# AgnusAdaptor.net
KiCad netlist of a schematic drawn in EAGLE
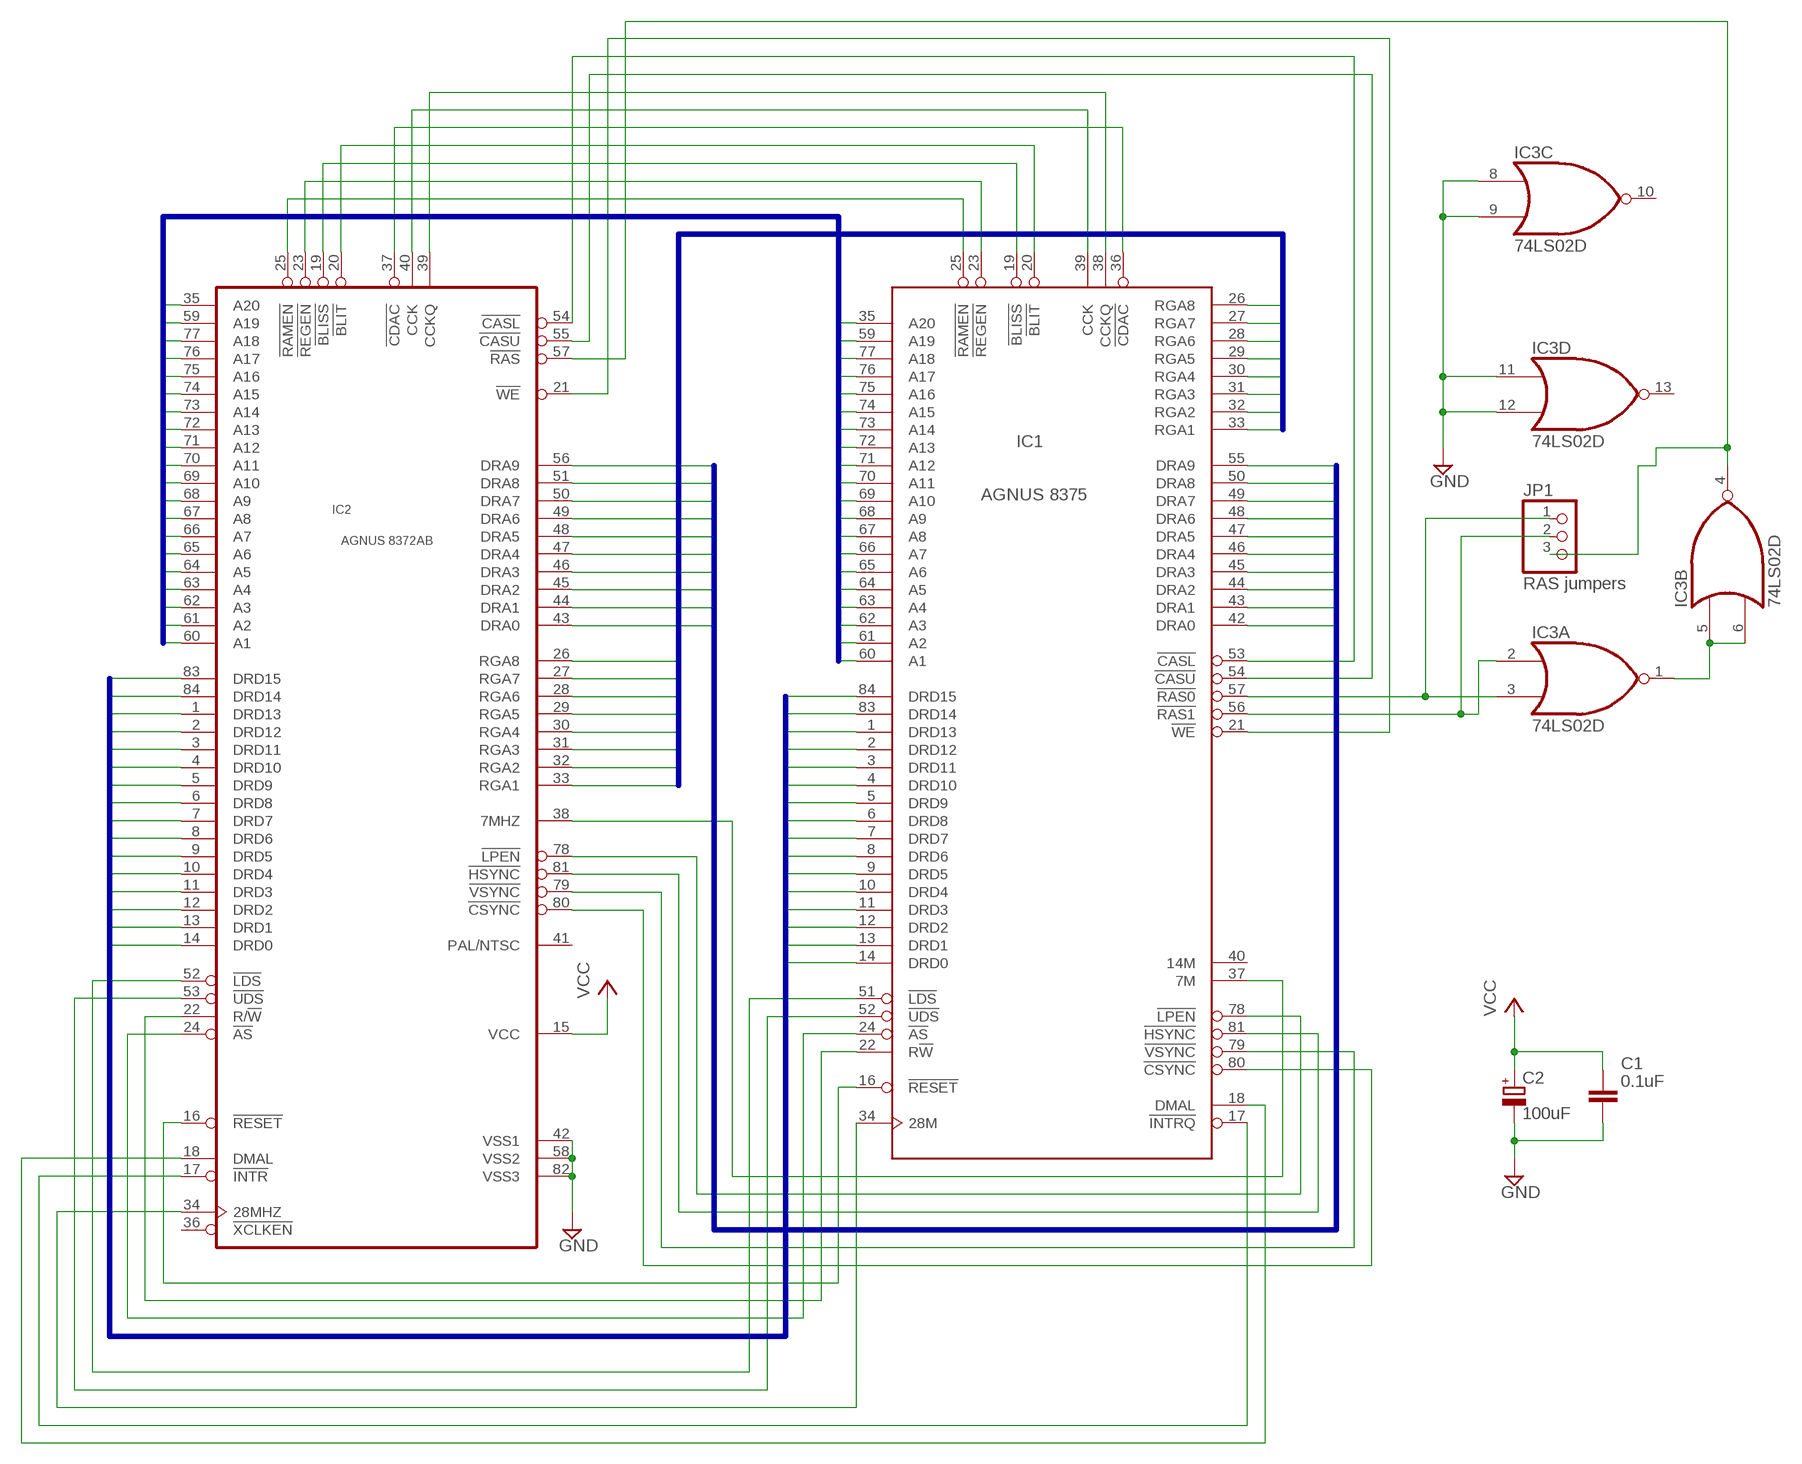
[diagram p0: schematic, sheet 1]

(export (version "E")
  (design (tool "Eeschema 10.0.6"))
  (components
    (comp (ref "C1")
      (value "0.1uF")
      (footprint "eagle-import:CAPC2012X110")
      (libsource (lib "eagle-import") (part "CCHIP-0805(2012-METRIC)_"))
    )
    (comp (ref "C2")
      (value "100uF")
      (footprint "eagle-import:CAPAE830X1050N")
      (libsource (lib "eagle-import") (part "C-POLECAP-8.5MM_"))
    )
    (comp (ref "IC1")
      (value "AGNUS_8375_A500+_A600_THT")
      (footprint "eagle-import:PLCC84_T")
      (libsource (lib "eagle-import") (part "AGNUS_8375_A500+_A600_THT"))
    )
    (comp (ref "IC2")
      (value "A3000 Agnus Socket")
      (footprint "eagle-import:PLCC84_T")
      (libsource (lib "eagle-import") (part "AGNUS_8372AB_THT"))
    )
    (comp (ref "IC3")
      (value "74LS02D")
      (footprint "eagle-import:SO14")
      (libsource (lib "eagle-import") (part "7402DLS"))
    )
    (comp (ref "JP1")
      (value "RAS jumpers")
      (footprint "eagle-import:1X03")
      (libsource (lib "eagle-import") (part "PINHD-1X3"))
    )
  )
  (nets
    (net (code "1") (name "/A1") (class "Default")
      (node (ref "IC1") (pin "60") (pinfunction "A1_60") (pintype "input"))
      (node (ref "IC2") (pin "60") (pinfunction "A1_60") (pintype "input"))
    )
    (net (code "2") (name "/A2") (class "Default")
      (node (ref "IC1") (pin "61") (pinfunction "A2_61") (pintype "input"))
      (node (ref "IC2") (pin "61") (pinfunction "A2_61") (pintype "input"))
    )
    (net (code "3") (name "/A3") (class "Default")
      (node (ref "IC1") (pin "62") (pinfunction "A3_62") (pintype "input"))
      (node (ref "IC2") (pin "62") (pinfunction "A3_62") (pintype "input"))
    )
    (net (code "4") (name "/A4") (class "Default")
      (node (ref "IC1") (pin "63") (pinfunction "A4_63") (pintype "input"))
      (node (ref "IC2") (pin "63") (pinfunction "A4_63") (pintype "input"))
    )
    (net (code "5") (name "/A5") (class "Default")
      (node (ref "IC1") (pin "64") (pinfunction "A5_64") (pintype "input"))
      (node (ref "IC2") (pin "64") (pinfunction "A5_64") (pintype "input"))
    )
    (net (code "6") (name "/A6") (class "Default")
      (node (ref "IC1") (pin "65") (pinfunction "A6_65") (pintype "input"))
      (node (ref "IC2") (pin "65") (pinfunction "A6_65") (pintype "input"))
    )
    (net (code "7") (name "/A7") (class "Default")
      (node (ref "IC1") (pin "66") (pinfunction "A7_66") (pintype "input"))
      (node (ref "IC2") (pin "66") (pinfunction "A7_66") (pintype "input"))
    )
    (net (code "8") (name "/A8") (class "Default")
      (node (ref "IC1") (pin "67") (pinfunction "A8_67") (pintype "input"))
      (node (ref "IC2") (pin "67") (pinfunction "A8_67") (pintype "input"))
    )
    (net (code "9") (name "/A9") (class "Default")
      (node (ref "IC1") (pin "68") (pinfunction "A9_68") (pintype "input"))
      (node (ref "IC2") (pin "68") (pinfunction "A9_68") (pintype "input"))
    )
    (net (code "10") (name "/A10") (class "Default")
      (node (ref "IC1") (pin "69") (pinfunction "A10_69") (pintype "input"))
      (node (ref "IC2") (pin "69") (pinfunction "A10_69") (pintype "input"))
    )
    (net (code "11") (name "/A11") (class "Default")
      (node (ref "IC1") (pin "70") (pinfunction "A11_70") (pintype "input"))
      (node (ref "IC2") (pin "70") (pinfunction "A11_70") (pintype "input"))
    )
    (net (code "12") (name "/A12") (class "Default")
      (node (ref "IC1") (pin "71") (pinfunction "A12_71") (pintype "input"))
      (node (ref "IC2") (pin "71") (pinfunction "A12_71") (pintype "input"))
    )
    (net (code "13") (name "/A13") (class "Default")
      (node (ref "IC1") (pin "72") (pinfunction "A13_72") (pintype "input"))
      (node (ref "IC2") (pin "72") (pinfunction "A13_72") (pintype "input"))
    )
    (net (code "14") (name "/A14") (class "Default")
      (node (ref "IC1") (pin "73") (pinfunction "A14_73") (pintype "input"))
      (node (ref "IC2") (pin "73") (pinfunction "A14_73") (pintype "input"))
    )
    (net (code "15") (name "/A15") (class "Default")
      (node (ref "IC1") (pin "74") (pinfunction "A15_74") (pintype "input"))
      (node (ref "IC2") (pin "74") (pinfunction "A15_74") (pintype "input"))
    )
    (net (code "16") (name "/A16") (class "Default")
      (node (ref "IC1") (pin "75") (pinfunction "A16_75") (pintype "input"))
      (node (ref "IC2") (pin "75") (pinfunction "A16_75") (pintype "input"))
    )
    (net (code "17") (name "/A17") (class "Default")
      (node (ref "IC1") (pin "76") (pinfunction "A17_76") (pintype "input"))
      (node (ref "IC2") (pin "76") (pinfunction "A17_76") (pintype "input"))
    )
    (net (code "18") (name "/A18") (class "Default")
      (node (ref "IC1") (pin "77") (pinfunction "A18_77") (pintype "input"))
      (node (ref "IC2") (pin "77") (pinfunction "A18_77") (pintype "input"))
    )
    (net (code "19") (name "/A19") (class "Default")
      (node (ref "IC1") (pin "59") (pinfunction "A19_59") (pintype "input"))
      (node (ref "IC2") (pin "59") (pinfunction "A19_59") (pintype "input"))
    )
    (net (code "20") (name "/A20") (class "Default")
      (node (ref "IC1") (pin "35") (pinfunction "A20_35") (pintype "input"))
      (node (ref "IC2") (pin "35") (pinfunction "A20_35") (pintype "input"))
    )
    (net (code "21") (name "/DRA0") (class "Default")
      (node (ref "IC1") (pin "42") (pinfunction "DRA0_42") (pintype "output"))
      (node (ref "IC2") (pin "43") (pinfunction "DRA0_43") (pintype "output"))
    )
    (net (code "22") (name "/DRA1") (class "Default")
      (node (ref "IC1") (pin "43") (pinfunction "DRA1_43") (pintype "output"))
      (node (ref "IC2") (pin "44") (pinfunction "DRA1_44") (pintype "output"))
    )
    (net (code "23") (name "/DRA2") (class "Default")
      (node (ref "IC1") (pin "44") (pinfunction "DRA2_44") (pintype "output"))
      (node (ref "IC2") (pin "45") (pinfunction "DRA2_45") (pintype "output"))
    )
    (net (code "24") (name "/DRA3") (class "Default")
      (node (ref "IC1") (pin "45") (pinfunction "DRA3_45") (pintype "output"))
      (node (ref "IC2") (pin "46") (pinfunction "DRA3_46") (pintype "output"))
    )
    (net (code "25") (name "/DRA4") (class "Default")
      (node (ref "IC1") (pin "46") (pinfunction "DRA4_46") (pintype "output"))
      (node (ref "IC2") (pin "47") (pinfunction "DRA4_47") (pintype "output"))
    )
    (net (code "26") (name "/DRA5") (class "Default")
      (node (ref "IC1") (pin "47") (pinfunction "DRA5_47") (pintype "output"))
      (node (ref "IC2") (pin "48") (pinfunction "DRA5_48") (pintype "output"))
    )
    (net (code "27") (name "/DRA6") (class "Default")
      (node (ref "IC1") (pin "48") (pinfunction "DRA6_48") (pintype "output"))
      (node (ref "IC2") (pin "49") (pinfunction "DRA6_49") (pintype "output"))
    )
    (net (code "28") (name "/DRA7") (class "Default")
      (node (ref "IC1") (pin "49") (pinfunction "DRA7_49") (pintype "output"))
      (node (ref "IC2") (pin "50") (pinfunction "DRA7_50") (pintype "output"))
    )
    (net (code "29") (name "/DRA8") (class "Default")
      (node (ref "IC1") (pin "50") (pinfunction "DRA8_50") (pintype "output"))
      (node (ref "IC2") (pin "51") (pinfunction "DRA8_51") (pintype "output"))
    )
    (net (code "30") (name "/DRA9") (class "Default")
      (node (ref "IC1") (pin "55") (pinfunction "DRA9_55") (pintype "output"))
      (node (ref "IC2") (pin "56") (pinfunction "DRA9_56") (pintype "output"))
    )
    (net (code "31") (name "/DRD0") (class "Default")
      (node (ref "IC1") (pin "14") (pinfunction "DRD0_14") (pintype "bidirectional"))
      (node (ref "IC2") (pin "14") (pinfunction "DRD0_14") (pintype "bidirectional"))
    )
    (net (code "32") (name "/DRD1") (class "Default")
      (node (ref "IC1") (pin "13") (pinfunction "DRD1_13") (pintype "bidirectional"))
      (node (ref "IC2") (pin "13") (pinfunction "DRD1_13") (pintype "bidirectional"))
    )
    (net (code "33") (name "/DRD2") (class "Default")
      (node (ref "IC1") (pin "12") (pinfunction "DRD2_12") (pintype "bidirectional"))
      (node (ref "IC2") (pin "12") (pinfunction "DRD2_12") (pintype "bidirectional"))
    )
    (net (code "34") (name "/DRD3") (class "Default")
      (node (ref "IC1") (pin "11") (pinfunction "DRD3_11") (pintype "bidirectional"))
      (node (ref "IC2") (pin "11") (pinfunction "DRD3_11") (pintype "bidirectional"))
    )
    (net (code "35") (name "/DRD4") (class "Default")
      (node (ref "IC1") (pin "10") (pinfunction "DRD4_10") (pintype "bidirectional"))
      (node (ref "IC2") (pin "10") (pinfunction "DRD4_10") (pintype "bidirectional"))
    )
    (net (code "36") (name "/DRD5") (class "Default")
      (node (ref "IC1") (pin "9") (pinfunction "DRD5_9") (pintype "bidirectional"))
      (node (ref "IC2") (pin "9") (pinfunction "DRD5_9") (pintype "bidirectional"))
    )
    (net (code "37") (name "/DRD6") (class "Default")
      (node (ref "IC1") (pin "8") (pinfunction "DRD6_8") (pintype "bidirectional"))
      (node (ref "IC2") (pin "8") (pinfunction "DRD6_8") (pintype "bidirectional"))
    )
    (net (code "38") (name "/DRD7") (class "Default")
      (node (ref "IC1") (pin "7") (pinfunction "DRD7_7") (pintype "bidirectional"))
      (node (ref "IC2") (pin "7") (pinfunction "DRD7_7") (pintype "bidirectional"))
    )
    (net (code "39") (name "/DRD8") (class "Default")
      (node (ref "IC1") (pin "6") (pinfunction "DRD8_6") (pintype "bidirectional"))
      (node (ref "IC2") (pin "6") (pinfunction "DRD8_6") (pintype "bidirectional"))
    )
    (net (code "40") (name "/DRD9") (class "Default")
      (node (ref "IC1") (pin "5") (pinfunction "DRD9_5") (pintype "bidirectional"))
      (node (ref "IC2") (pin "5") (pinfunction "DRD9_5") (pintype "bidirectional"))
    )
    (net (code "41") (name "/DRD10") (class "Default")
      (node (ref "IC1") (pin "4") (pinfunction "DRD10_4") (pintype "bidirectional"))
      (node (ref "IC2") (pin "4") (pinfunction "DRD10_4") (pintype "bidirectional"))
    )
    (net (code "42") (name "/DRD11") (class "Default")
      (node (ref "IC1") (pin "3") (pinfunction "DRD11_3") (pintype "bidirectional"))
      (node (ref "IC2") (pin "3") (pinfunction "DRD11_3") (pintype "bidirectional"))
    )
    (net (code "43") (name "/DRD12") (class "Default")
      (node (ref "IC1") (pin "2") (pinfunction "DRD12_2") (pintype "bidirectional"))
      (node (ref "IC2") (pin "2") (pinfunction "DRD12_2") (pintype "bidirectional"))
    )
    (net (code "44") (name "/DRD13") (class "Default")
      (node (ref "IC1") (pin "1") (pinfunction "DRD13_1") (pintype "bidirectional"))
      (node (ref "IC2") (pin "1") (pinfunction "DRD13_1") (pintype "bidirectional"))
    )
    (net (code "45") (name "/DRD14") (class "Default")
      (node (ref "IC1") (pin "83") (pinfunction "DRD14_83") (pintype "bidirectional"))
      (node (ref "IC2") (pin "84") (pinfunction "DRD14_84") (pintype "bidirectional"))
    )
    (net (code "46") (name "/DRD15") (class "Default")
      (node (ref "IC1") (pin "84") (pinfunction "DRD15_84") (pintype "bidirectional"))
      (node (ref "IC2") (pin "83") (pinfunction "DRD15_83") (pintype "bidirectional"))
    )
    (net (code "47") (name "/RGA1") (class "Default")
      (node (ref "IC1") (pin "33") (pinfunction "RGA1_33") (pintype "output"))
      (node (ref "IC2") (pin "33") (pinfunction "RGA1_33") (pintype "bidirectional"))
    )
    (net (code "48") (name "/RGA2") (class "Default")
      (node (ref "IC1") (pin "32") (pinfunction "RGA2_32") (pintype "output"))
      (node (ref "IC2") (pin "32") (pinfunction "RGA2_32") (pintype "bidirectional"))
    )
    (net (code "49") (name "/RGA3") (class "Default")
      (node (ref "IC1") (pin "31") (pinfunction "RGA3_31") (pintype "output"))
      (node (ref "IC2") (pin "31") (pinfunction "RGA3_31") (pintype "bidirectional"))
    )
    (net (code "50") (name "/RGA4") (class "Default")
      (node (ref "IC1") (pin "30") (pinfunction "RGA4_30") (pintype "output"))
      (node (ref "IC2") (pin "30") (pinfunction "RGA4_30") (pintype "bidirectional"))
    )
    (net (code "51") (name "/RGA5") (class "Default")
      (node (ref "IC1") (pin "29") (pinfunction "RGA5_29") (pintype "output"))
      (node (ref "IC2") (pin "29") (pinfunction "RGA5_29") (pintype "bidirectional"))
    )
    (net (code "52") (name "/RGA6") (class "Default")
      (node (ref "IC1") (pin "28") (pinfunction "RGA6_28") (pintype "output"))
      (node (ref "IC2") (pin "28") (pinfunction "RGA6_28") (pintype "bidirectional"))
    )
    (net (code "53") (name "/RGA7") (class "Default")
      (node (ref "IC1") (pin "27") (pinfunction "RGA7_27") (pintype "output"))
      (node (ref "IC2") (pin "27") (pinfunction "RGA7_27") (pintype "bidirectional"))
    )
    (net (code "54") (name "/RGA8") (class "Default")
      (node (ref "IC1") (pin "26") (pinfunction "RGA8_26") (pintype "output"))
      (node (ref "IC2") (pin "26") (pinfunction "RGA8_26") (pintype "bidirectional"))
    )
    (net (code "55") (name "GND") (class "Default")
      (node (ref "C1") (pin "2") (pinfunction "2_2") (pintype "passive"))
      (node (ref "C2") (pin "2") (pinfunction "-_2") (pintype "passive"))
      (node (ref "IC2") (pin "42") (pinfunction "VSS1_42") (pintype "power_in"))
      (node (ref "IC2") (pin "58") (pinfunction "VSS2_58") (pintype "power_in"))
      (node (ref "IC2") (pin "82") (pinfunction "VSS3_82") (pintype "power_in"))
      (node (ref "IC3") (pin "11") (pinfunction "I0_11") (pintype "input"))
      (node (ref "IC3") (pin "12") (pinfunction "I1_12") (pintype "input"))
      (node (ref "IC3") (pin "8") (pinfunction "I0_8") (pintype "input"))
      (node (ref "IC3") (pin "9") (pinfunction "I1_9") (pintype "input"))
    )
    (net (code "56") (name "Net-(IC1A-7M)") (class "Default")
      (node (ref "IC1") (pin "37") (pinfunction "7M_37") (pintype "output"))
      (node (ref "IC2") (pin "38") (pinfunction "7MHZ_38") (pintype "output"))
    )
    (net (code "57") (name "Net-(IC1A-28M)") (class "Default")
      (node (ref "IC1") (pin "34") (pinfunction "28M_34") (pintype "input"))
      (node (ref "IC2") (pin "34") (pinfunction "28MHZ_34") (pintype "input"))
    )
    (net (code "58") (name "Net-(IC1A-CCK)") (class "Default")
      (node (ref "IC1") (pin "39") (pinfunction "CCK_39") (pintype "output"))
      (node (ref "IC2") (pin "40") (pinfunction "CCK_40") (pintype "output"))
    )
    (net (code "59") (name "Net-(IC1A-CCKQ)") (class "Default")
      (node (ref "IC1") (pin "38") (pinfunction "CCKQ_38") (pintype "output"))
      (node (ref "IC2") (pin "39") (pinfunction "CCKQ_39") (pintype "output"))
    )
    (net (code "60") (name "Net-(IC1A-DMAL)") (class "Default")
      (node (ref "IC1") (pin "18") (pinfunction "DMAL_18") (pintype "input"))
      (node (ref "IC2") (pin "18") (pinfunction "DMAL_18") (pintype "input"))
    )
    (net (code "61") (name "Net-(IC1A-R~{W})") (class "Default")
      (node (ref "IC1") (pin "22") (pinfunction "R~{W}_22") (pintype "input"))
      (node (ref "IC2") (pin "22") (pinfunction "R/~{W}_22") (pintype "input"))
    )
    (net (code "62") (name "Net-(IC1A-~{AS})") (class "Default")
      (node (ref "IC1") (pin "24") (pinfunction "~{AS}_24") (pintype "input"))
      (node (ref "IC2") (pin "24") (pinfunction "~{AS}_24") (pintype "input"))
    )
    (net (code "63") (name "Net-(IC1A-~{BLISS})") (class "Default")
      (node (ref "IC1") (pin "19") (pinfunction "~{BLISS}_19") (pintype "output"))
      (node (ref "IC2") (pin "19") (pinfunction "~{BLISS}_19") (pintype "input"))
    )
    (net (code "64") (name "Net-(IC1A-~{BLIT})") (class "Default")
      (node (ref "IC1") (pin "20") (pinfunction "~{BLIT}_20") (pintype "output"))
      (node (ref "IC2") (pin "20") (pinfunction "~{BLIT}_20") (pintype "output"))
    )
    (net (code "65") (name "Net-(IC1A-~{CASL})") (class "Default")
      (node (ref "IC1") (pin "53") (pinfunction "~{CASL}_53") (pintype "output"))
      (node (ref "IC2") (pin "54") (pinfunction "~{CASL}_54") (pintype "output"))
    )
    (net (code "66") (name "Net-(IC1A-~{CASU})") (class "Default")
      (node (ref "IC1") (pin "54") (pinfunction "~{CASU}_54") (pintype "output"))
      (node (ref "IC2") (pin "55") (pinfunction "~{CASU}_55") (pintype "output"))
    )
    (net (code "67") (name "Net-(IC1A-~{CDAC})") (class "Default")
      (node (ref "IC1") (pin "36") (pinfunction "~{CDAC}_36") (pintype "output"))
      (node (ref "IC2") (pin "37") (pinfunction "~{CDAC}_37") (pintype "output"))
    )
    (net (code "68") (name "Net-(IC1A-~{CSYNC})") (class "Default")
      (node (ref "IC1") (pin "80") (pinfunction "~{CSYNC}_80") (pintype "output"))
      (node (ref "IC2") (pin "80") (pinfunction "~{CSYNC}_80") (pintype "output"))
    )
    (net (code "69") (name "Net-(IC1A-~{HSYNC})") (class "Default")
      (node (ref "IC1") (pin "81") (pinfunction "~{HSYNC}_81") (pintype "output"))
      (node (ref "IC2") (pin "81") (pinfunction "~{HSYNC}_81") (pintype "output"))
    )
    (net (code "70") (name "Net-(IC1A-~{INTRQ})") (class "Default")
      (node (ref "IC1") (pin "17") (pinfunction "~{INTRQ}_17") (pintype "output"))
      (node (ref "IC2") (pin "17") (pinfunction "~{INTR}_17") (pintype "output"))
    )
    (net (code "71") (name "Net-(IC1A-~{LDS})") (class "Default")
      (node (ref "IC1") (pin "51") (pinfunction "~{LDS}_51") (pintype "input"))
      (node (ref "IC2") (pin "52") (pinfunction "~{LDS}_52") (pintype "input"))
    )
    (net (code "72") (name "Net-(IC1A-~{LPEN})") (class "Default")
      (node (ref "IC1") (pin "78") (pinfunction "~{LPEN}_78") (pintype "input"))
      (node (ref "IC2") (pin "78") (pinfunction "~{LPEN}_78") (pintype "input"))
    )
    (net (code "73") (name "Net-(IC1A-~{RAMEN})") (class "Default")
      (node (ref "IC1") (pin "25") (pinfunction "~{RAMEN}_25") (pintype "output"))
      (node (ref "IC2") (pin "25") (pinfunction "~{RAMEN}_25") (pintype "input"))
    )
    (net (code "74") (name "Net-(IC1A-~{RAS0})") (class "Default")
      (node (ref "IC1") (pin "57") (pinfunction "~{RAS0}_57") (pintype "output"))
      (node (ref "IC3") (pin "3") (pinfunction "I1_3") (pintype "input"))
      (node (ref "JP1") (pin "1") (pinfunction "1_1") (pintype "passive"))
    )
    (net (code "75") (name "Net-(IC1A-~{RAS1})") (class "Default")
      (node (ref "IC1") (pin "56") (pinfunction "~{RAS1}_56") (pintype "output"))
      (node (ref "IC3") (pin "2") (pinfunction "I0_2") (pintype "input"))
      (node (ref "JP1") (pin "2") (pinfunction "2_2") (pintype "passive"))
    )
    (net (code "76") (name "Net-(IC1A-~{REGEN})") (class "Default")
      (node (ref "IC1") (pin "23") (pinfunction "~{REGEN}_23") (pintype "output"))
      (node (ref "IC2") (pin "23") (pinfunction "~{REGEN}_23") (pintype "input"))
    )
    (net (code "77") (name "Net-(IC1A-~{RESET})") (class "Default")
      (node (ref "IC1") (pin "16") (pinfunction "~{RESET}_16") (pintype "input"))
      (node (ref "IC2") (pin "16") (pinfunction "~{RESET}_16") (pintype "input"))
    )
    (net (code "78") (name "Net-(IC1A-~{UDS})") (class "Default")
      (node (ref "IC1") (pin "52") (pinfunction "~{UDS}_52") (pintype "input"))
      (node (ref "IC2") (pin "53") (pinfunction "~{UDS}_53") (pintype "input"))
    )
    (net (code "79") (name "Net-(IC1A-~{VSYNC})") (class "Default")
      (node (ref "IC1") (pin "79") (pinfunction "~{VSYNC}_79") (pintype "output"))
      (node (ref "IC2") (pin "79") (pinfunction "~{VSYNC}_79") (pintype "output"))
    )
    (net (code "80") (name "Net-(IC1A-~{WE})") (class "Default")
      (node (ref "IC1") (pin "21") (pinfunction "~{WE}_21") (pintype "output"))
      (node (ref "IC2") (pin "21") (pinfunction "~{WE}_21") (pintype "output"))
    )
    (net (code "81") (name "Net-(IC2-~{RAS})") (class "Default")
      (node (ref "IC2") (pin "57") (pinfunction "~{RAS}_57") (pintype "output"))
      (node (ref "IC3") (pin "4") (pinfunction "O_4") (pintype "output"))
      (node (ref "JP1") (pin "3") (pinfunction "3_3") (pintype "passive"))
    )
    (net (code "82") (name "Net-(IC3A-O)") (class "Default")
      (node (ref "IC3") (pin "1") (pinfunction "O_1") (pintype "output"))
      (node (ref "IC3") (pin "5") (pinfunction "I0_5") (pintype "input"))
      (node (ref "IC3") (pin "6") (pinfunction "I1_6") (pintype "input"))
    )
    (net (code "83") (name "VCC") (class "Default")
      (node (ref "C1") (pin "1") (pinfunction "1_1") (pintype "passive"))
      (node (ref "C2") (pin "1") (pinfunction "+_1") (pintype "passive"))
      (node (ref "IC2") (pin "15") (pinfunction "VCC_15") (pintype "power_in"))
    )
    (net (code "84") (name "unconnected-(IC1A-14M-Pad40)") (class "Default")
      (node (ref "IC1") (pin "40") (pinfunction "14M_40") (pintype "output"))
    )
    (net (code "85") (name "unconnected-(IC2-PAL{slash}NTSC-Pad41)") (class "Default")
      (node (ref "IC2") (pin "41") (pinfunction "PAL/NTSC_41") (pintype "input"))
    )
    (net (code "86") (name "unconnected-(IC2-~{XCLKEN}-Pad36)") (class "Default")
      (node (ref "IC2") (pin "36") (pinfunction "~{XCLKEN}_36") (pintype "input"))
    )
    (net (code "87") (name "unconnected-(IC3C-O-Pad10)") (class "Default")
      (node (ref "IC3") (pin "10") (pinfunction "O_10") (pintype "output"))
    )
    (net (code "88") (name "unconnected-(IC3D-O-Pad13)") (class "Default")
      (node (ref "IC3") (pin "13") (pinfunction "O_13") (pintype "output"))
    )
  )
)
